# PCE-TG16.net
KiCad netlist of a schematic drawn in EAGLE
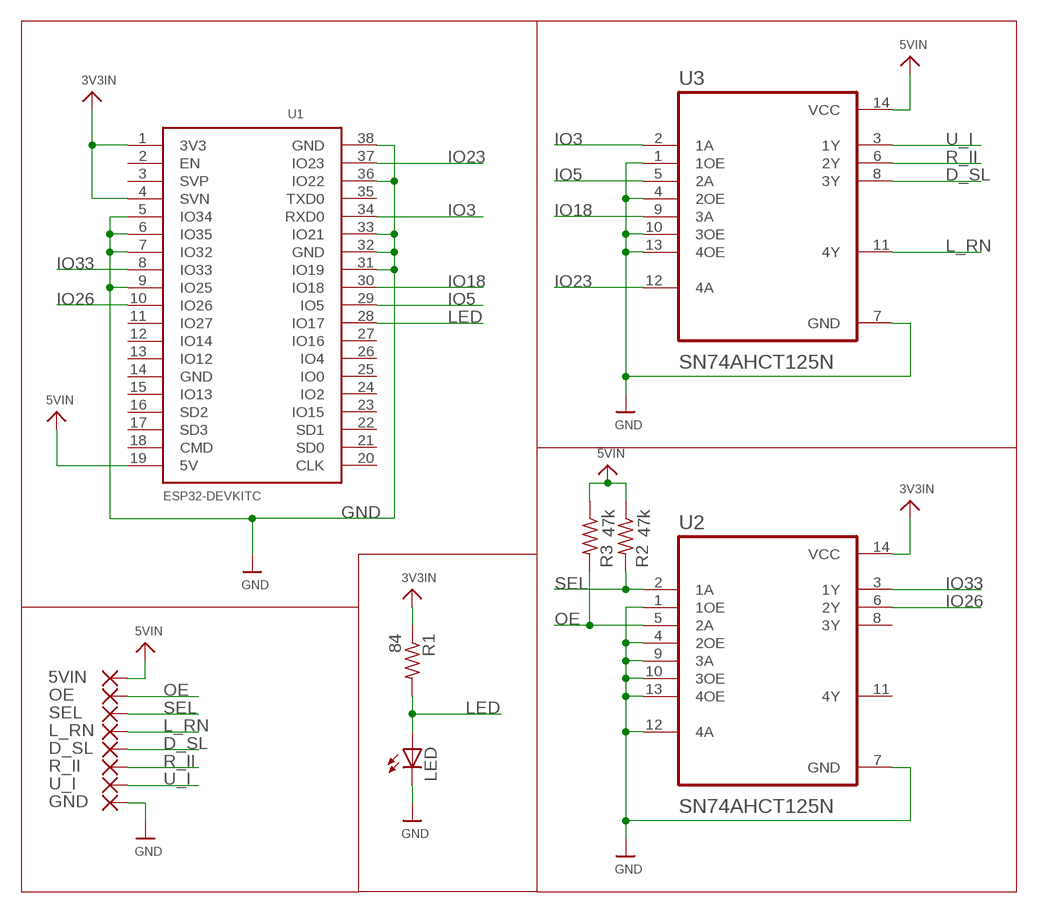
[diagram p0: schematic, sheet 1]

(export (version "E")
  (design (tool "Eeschema 10.0.6"))
  (components
    (comp (ref "5VIN")
      (value "SMD5")
      (footprint "eagle-import:SMD2,54-5,08")
      (libsource (lib "eagle-import") (part "SMD5"))
    )
    (comp (ref "D_SL")
      (value "SMD5")
      (footprint "eagle-import:SMD2,54-5,08")
      (libsource (lib "eagle-import") (part "SMD5"))
    )
    (comp (ref "GND")
      (value "SMD5")
      (footprint "eagle-import:SMD2,54-5,08")
      (libsource (lib "eagle-import") (part "SMD5"))
    )
    (comp (ref "LED")
      (value "LEDCHIPLED_1206")
      (footprint "eagle-import:CHIPLED_1206")
      (libsource (lib "eagle-import") (part "LEDCHIPLED_1206"))
    )
    (comp (ref "L_RN")
      (value "SMD5")
      (footprint "eagle-import:SMD2,54-5,08")
      (libsource (lib "eagle-import") (part "SMD5"))
    )
    (comp (ref "OE")
      (value "SMD5")
      (footprint "eagle-import:SMD2,54-5,08")
      (libsource (lib "eagle-import") (part "SMD5"))
    )
    (comp (ref "R1")
      (value "84")
      (footprint "eagle-import:R1206")
      (libsource (lib "eagle-import") (part "R-US_R1206"))
    )
    (comp (ref "R2")
      (value "47k")
      (footprint "eagle-import:R1206")
      (libsource (lib "eagle-import") (part "adafruit_420_R-US_R1206"))
    )
    (comp (ref "R3")
      (value "47k")
      (footprint "eagle-import:R1206")
      (libsource (lib "eagle-import") (part "adafruit_420_R-US_R1206"))
    )
    (comp (ref "R_II")
      (value "SMD5")
      (footprint "eagle-import:SMD2,54-5,08")
      (libsource (lib "eagle-import") (part "SMD5"))
    )
    (comp (ref "SEL")
      (value "SMD5")
      (footprint "eagle-import:SMD2,54-5,08")
      (libsource (lib "eagle-import") (part "SMD5"))
    )
    (comp (ref "U1")
      (value "ESP32DEVKITC")
      (footprint "eagle-import:ESP32-DEVKITC")
      (libsource (lib "eagle-import") (part "ESP32DEVKITC"))
    )
    (comp (ref "U2")
      (value "SN74AHCT125N")
      (footprint "eagle-import:DIP794W45P254L1969H508Q14")
      (fields (field (name "MF") "Texas Instruments"))
      (libsource (lib "eagle-import") (part "SN74AHCT125N"))
    )
    (comp (ref "U3")
      (value "SN74AHCT125N")
      (footprint "eagle-import:DIP794W45P254L1969H508Q14")
      (fields (field (name "MF") "Texas Instruments"))
      (libsource (lib "eagle-import") (part "SN74AHCT125N"))
    )
    (comp (ref "U_I")
      (value "SMD5")
      (footprint "eagle-import:SMD2,54-5,08")
      (libsource (lib "eagle-import") (part "SMD5"))
    )
  )
  (nets
    (net (code "1") (name "/D_SL") (class "Default")
      (node (ref "D_SL") (pin "1") (pinfunction "P_1") (pintype "passive"))
      (node (ref "U3") (pin "8") (pinfunction "3Y_8") (pintype "output"))
    )
    (net (code "2") (name "/IO3") (class "Default")
      (node (ref "U1") (pin "34") (pinfunction "RXD0_34") (pintype "bidirectional"))
      (node (ref "U3") (pin "2") (pinfunction "1A_2") (pintype "input"))
    )
    (net (code "3") (name "/IO5") (class "Default")
      (node (ref "U1") (pin "29") (pinfunction "IO5_29") (pintype "bidirectional"))
      (node (ref "U3") (pin "5") (pinfunction "2A_5") (pintype "input"))
    )
    (net (code "4") (name "/IO18") (class "Default")
      (node (ref "U1") (pin "30") (pinfunction "IO18_30") (pintype "bidirectional"))
      (node (ref "U3") (pin "9") (pinfunction "3A_9") (pintype "input"))
    )
    (net (code "5") (name "/IO23") (class "Default")
      (node (ref "U1") (pin "37") (pinfunction "IO23_37") (pintype "bidirectional"))
      (node (ref "U3") (pin "12") (pinfunction "4A_12") (pintype "bidirectional"))
    )
    (net (code "6") (name "/IO26") (class "Default")
      (node (ref "U1") (pin "10") (pinfunction "IO26_10") (pintype "bidirectional"))
      (node (ref "U2") (pin "6") (pinfunction "2Y_6") (pintype "output"))
    )
    (net (code "7") (name "/IO33") (class "Default")
      (node (ref "U1") (pin "8") (pinfunction "IO33_8") (pintype "bidirectional"))
      (node (ref "U2") (pin "3") (pinfunction "1Y_3") (pintype "output"))
    )
    (net (code "8") (name "/LED") (class "Default")
      (node (ref "LED") (pin "A") (pinfunction "A_A") (pintype "passive"))
      (node (ref "R1") (pin "2") (pinfunction "2_2") (pintype "passive"))
      (node (ref "U1") (pin "28") (pinfunction "IO17_28") (pintype "bidirectional"))
    )
    (net (code "9") (name "/L_RN") (class "Default")
      (node (ref "L_RN") (pin "1") (pinfunction "P_1") (pintype "passive"))
      (node (ref "U3") (pin "11") (pinfunction "4Y_11") (pintype "output"))
    )
    (net (code "10") (name "/OE") (class "Default")
      (node (ref "OE") (pin "1") (pinfunction "P_1") (pintype "passive"))
      (node (ref "R3") (pin "2") (pinfunction "2_2") (pintype "passive"))
      (node (ref "U2") (pin "5") (pinfunction "2A_5") (pintype "input"))
    )
    (net (code "11") (name "/R_II") (class "Default")
      (node (ref "R_II") (pin "1") (pinfunction "P_1") (pintype "passive"))
      (node (ref "U3") (pin "6") (pinfunction "2Y_6") (pintype "output"))
    )
    (net (code "12") (name "/SEL") (class "Default")
      (node (ref "R2") (pin "2") (pinfunction "2_2") (pintype "passive"))
      (node (ref "SEL") (pin "1") (pinfunction "P_1") (pintype "passive"))
      (node (ref "U2") (pin "2") (pinfunction "1A_2") (pintype "input"))
    )
    (net (code "13") (name "/U_I") (class "Default")
      (node (ref "U3") (pin "3") (pinfunction "1Y_3") (pintype "output"))
      (node (ref "U_I") (pin "1") (pinfunction "P_1") (pintype "passive"))
    )
    (net (code "14") (name "3V3IN") (class "Default")
      (node (ref "R1") (pin "1") (pinfunction "1_1") (pintype "passive"))
      (node (ref "U1") (pin "1") (pinfunction "3V3_1") (pintype "bidirectional"))
      (node (ref "U1") (pin "4") (pinfunction "SVN_4") (pintype "bidirectional"))
      (node (ref "U2") (pin "14") (pinfunction "VCC_14") (pintype "power_in"))
    )
    (net (code "15") (name "5VIN") (class "Default")
      (node (ref "5VIN") (pin "1") (pinfunction "P_1") (pintype "passive"))
      (node (ref "R2") (pin "1") (pinfunction "1_1") (pintype "passive"))
      (node (ref "R3") (pin "1") (pinfunction "1_1") (pintype "passive"))
      (node (ref "U1") (pin "19") (pinfunction "5V_19") (pintype "bidirectional"))
      (node (ref "U3") (pin "14") (pinfunction "VCC_14") (pintype "power_in"))
    )
    (net (code "16") (name "GND") (class "Default")
      (node (ref "GND") (pin "1") (pinfunction "P_1") (pintype "passive"))
      (node (ref "LED") (pin "C") (pinfunction "C_C") (pintype "passive"))
      (node (ref "U1") (pin "31") (pinfunction "IO19_31") (pintype "bidirectional"))
      (node (ref "U1") (pin "32") (pinfunction "GND_32") (pintype "bidirectional"))
      (node (ref "U1") (pin "33") (pinfunction "IO21_33") (pintype "bidirectional"))
      (node (ref "U1") (pin "36") (pinfunction "IO22_36") (pintype "bidirectional"))
      (node (ref "U1") (pin "38") (pinfunction "GND_38") (pintype "bidirectional"))
      (node (ref "U1") (pin "5") (pinfunction "IO34_5") (pintype "bidirectional"))
      (node (ref "U1") (pin "6") (pinfunction "IO35_6") (pintype "bidirectional"))
      (node (ref "U1") (pin "7") (pinfunction "IO32_7") (pintype "bidirectional"))
      (node (ref "U1") (pin "9") (pinfunction "IO25_9") (pintype "bidirectional"))
      (node (ref "U2") (pin "1") (pinfunction "1OE_1") (pintype "input"))
      (node (ref "U2") (pin "10") (pinfunction "3OE_10") (pintype "input"))
      (node (ref "U2") (pin "12") (pinfunction "4A_12") (pintype "bidirectional"))
      (node (ref "U2") (pin "13") (pinfunction "4OE_13") (pintype "input"))
      (node (ref "U2") (pin "4") (pinfunction "2OE_4") (pintype "input"))
      (node (ref "U2") (pin "7") (pinfunction "GND_7") (pintype "power_in"))
      (node (ref "U2") (pin "9") (pinfunction "3A_9") (pintype "input"))
      (node (ref "U3") (pin "1") (pinfunction "1OE_1") (pintype "input"))
      (node (ref "U3") (pin "10") (pinfunction "3OE_10") (pintype "input"))
      (node (ref "U3") (pin "13") (pinfunction "4OE_13") (pintype "input"))
      (node (ref "U3") (pin "4") (pinfunction "2OE_4") (pintype "input"))
      (node (ref "U3") (pin "7") (pinfunction "GND_7") (pintype "power_in"))
    )
    (net (code "17") (name "unconnected-(U1-CLK-Pad20)") (class "Default")
      (node (ref "U1") (pin "20") (pinfunction "CLK_20") (pintype "bidirectional"))
    )
    (net (code "18") (name "unconnected-(U1-CMD-Pad18)") (class "Default")
      (node (ref "U1") (pin "18") (pinfunction "CMD_18") (pintype "bidirectional"))
    )
    (net (code "19") (name "unconnected-(U1-EN-Pad2)") (class "Default")
      (node (ref "U1") (pin "2") (pinfunction "EN_2") (pintype "bidirectional"))
    )
    (net (code "20") (name "unconnected-(U1-GND-Pad14)") (class "Default")
      (node (ref "U1") (pin "14") (pinfunction "GND_14") (pintype "bidirectional"))
    )
    (net (code "21") (name "unconnected-(U1-IO0-Pad25)") (class "Default")
      (node (ref "U1") (pin "25") (pinfunction "IO0_25") (pintype "bidirectional"))
    )
    (net (code "22") (name "unconnected-(U1-IO2-Pad24)") (class "Default")
      (node (ref "U1") (pin "24") (pinfunction "IO2_24") (pintype "bidirectional"))
    )
    (net (code "23") (name "unconnected-(U1-IO4-Pad26)") (class "Default")
      (node (ref "U1") (pin "26") (pinfunction "IO4_26") (pintype "bidirectional"))
    )
    (net (code "24") (name "unconnected-(U1-IO12-Pad13)") (class "Default")
      (node (ref "U1") (pin "13") (pinfunction "IO12_13") (pintype "bidirectional"))
    )
    (net (code "25") (name "unconnected-(U1-IO13-Pad15)") (class "Default")
      (node (ref "U1") (pin "15") (pinfunction "IO13_15") (pintype "bidirectional"))
    )
    (net (code "26") (name "unconnected-(U1-IO14-Pad12)") (class "Default")
      (node (ref "U1") (pin "12") (pinfunction "IO14_12") (pintype "bidirectional"))
    )
    (net (code "27") (name "unconnected-(U1-IO15-Pad23)") (class "Default")
      (node (ref "U1") (pin "23") (pinfunction "IO15_23") (pintype "bidirectional"))
    )
    (net (code "28") (name "unconnected-(U1-IO16-Pad27)") (class "Default")
      (node (ref "U1") (pin "27") (pinfunction "IO16_27") (pintype "bidirectional"))
    )
    (net (code "29") (name "unconnected-(U1-IO27-Pad11)") (class "Default")
      (node (ref "U1") (pin "11") (pinfunction "IO27_11") (pintype "bidirectional"))
    )
    (net (code "30") (name "unconnected-(U1-SD0-Pad21)") (class "Default")
      (node (ref "U1") (pin "21") (pinfunction "SD0_21") (pintype "bidirectional"))
    )
    (net (code "31") (name "unconnected-(U1-SD1-Pad22)") (class "Default")
      (node (ref "U1") (pin "22") (pinfunction "SD1_22") (pintype "bidirectional"))
    )
    (net (code "32") (name "unconnected-(U1-SD2-Pad16)") (class "Default")
      (node (ref "U1") (pin "16") (pinfunction "SD2_16") (pintype "bidirectional"))
    )
    (net (code "33") (name "unconnected-(U1-SD3-Pad17)") (class "Default")
      (node (ref "U1") (pin "17") (pinfunction "SD3_17") (pintype "bidirectional"))
    )
    (net (code "34") (name "unconnected-(U1-SVP-Pad3)") (class "Default")
      (node (ref "U1") (pin "3") (pinfunction "SVP_3") (pintype "bidirectional"))
    )
    (net (code "35") (name "unconnected-(U1-TXD0-Pad35)") (class "Default")
      (node (ref "U1") (pin "35") (pinfunction "TXD0_35") (pintype "bidirectional"))
    )
    (net (code "36") (name "unconnected-(U2-3Y-Pad8)") (class "Default")
      (node (ref "U2") (pin "8") (pinfunction "3Y_8") (pintype "output"))
    )
    (net (code "37") (name "unconnected-(U2-4Y-Pad11)") (class "Default")
      (node (ref "U2") (pin "11") (pinfunction "4Y_11") (pintype "output"))
    )
  )
)
